# Thermocouple_Schematic.net
KiCad netlist of a schematic drawn in EasyEDA
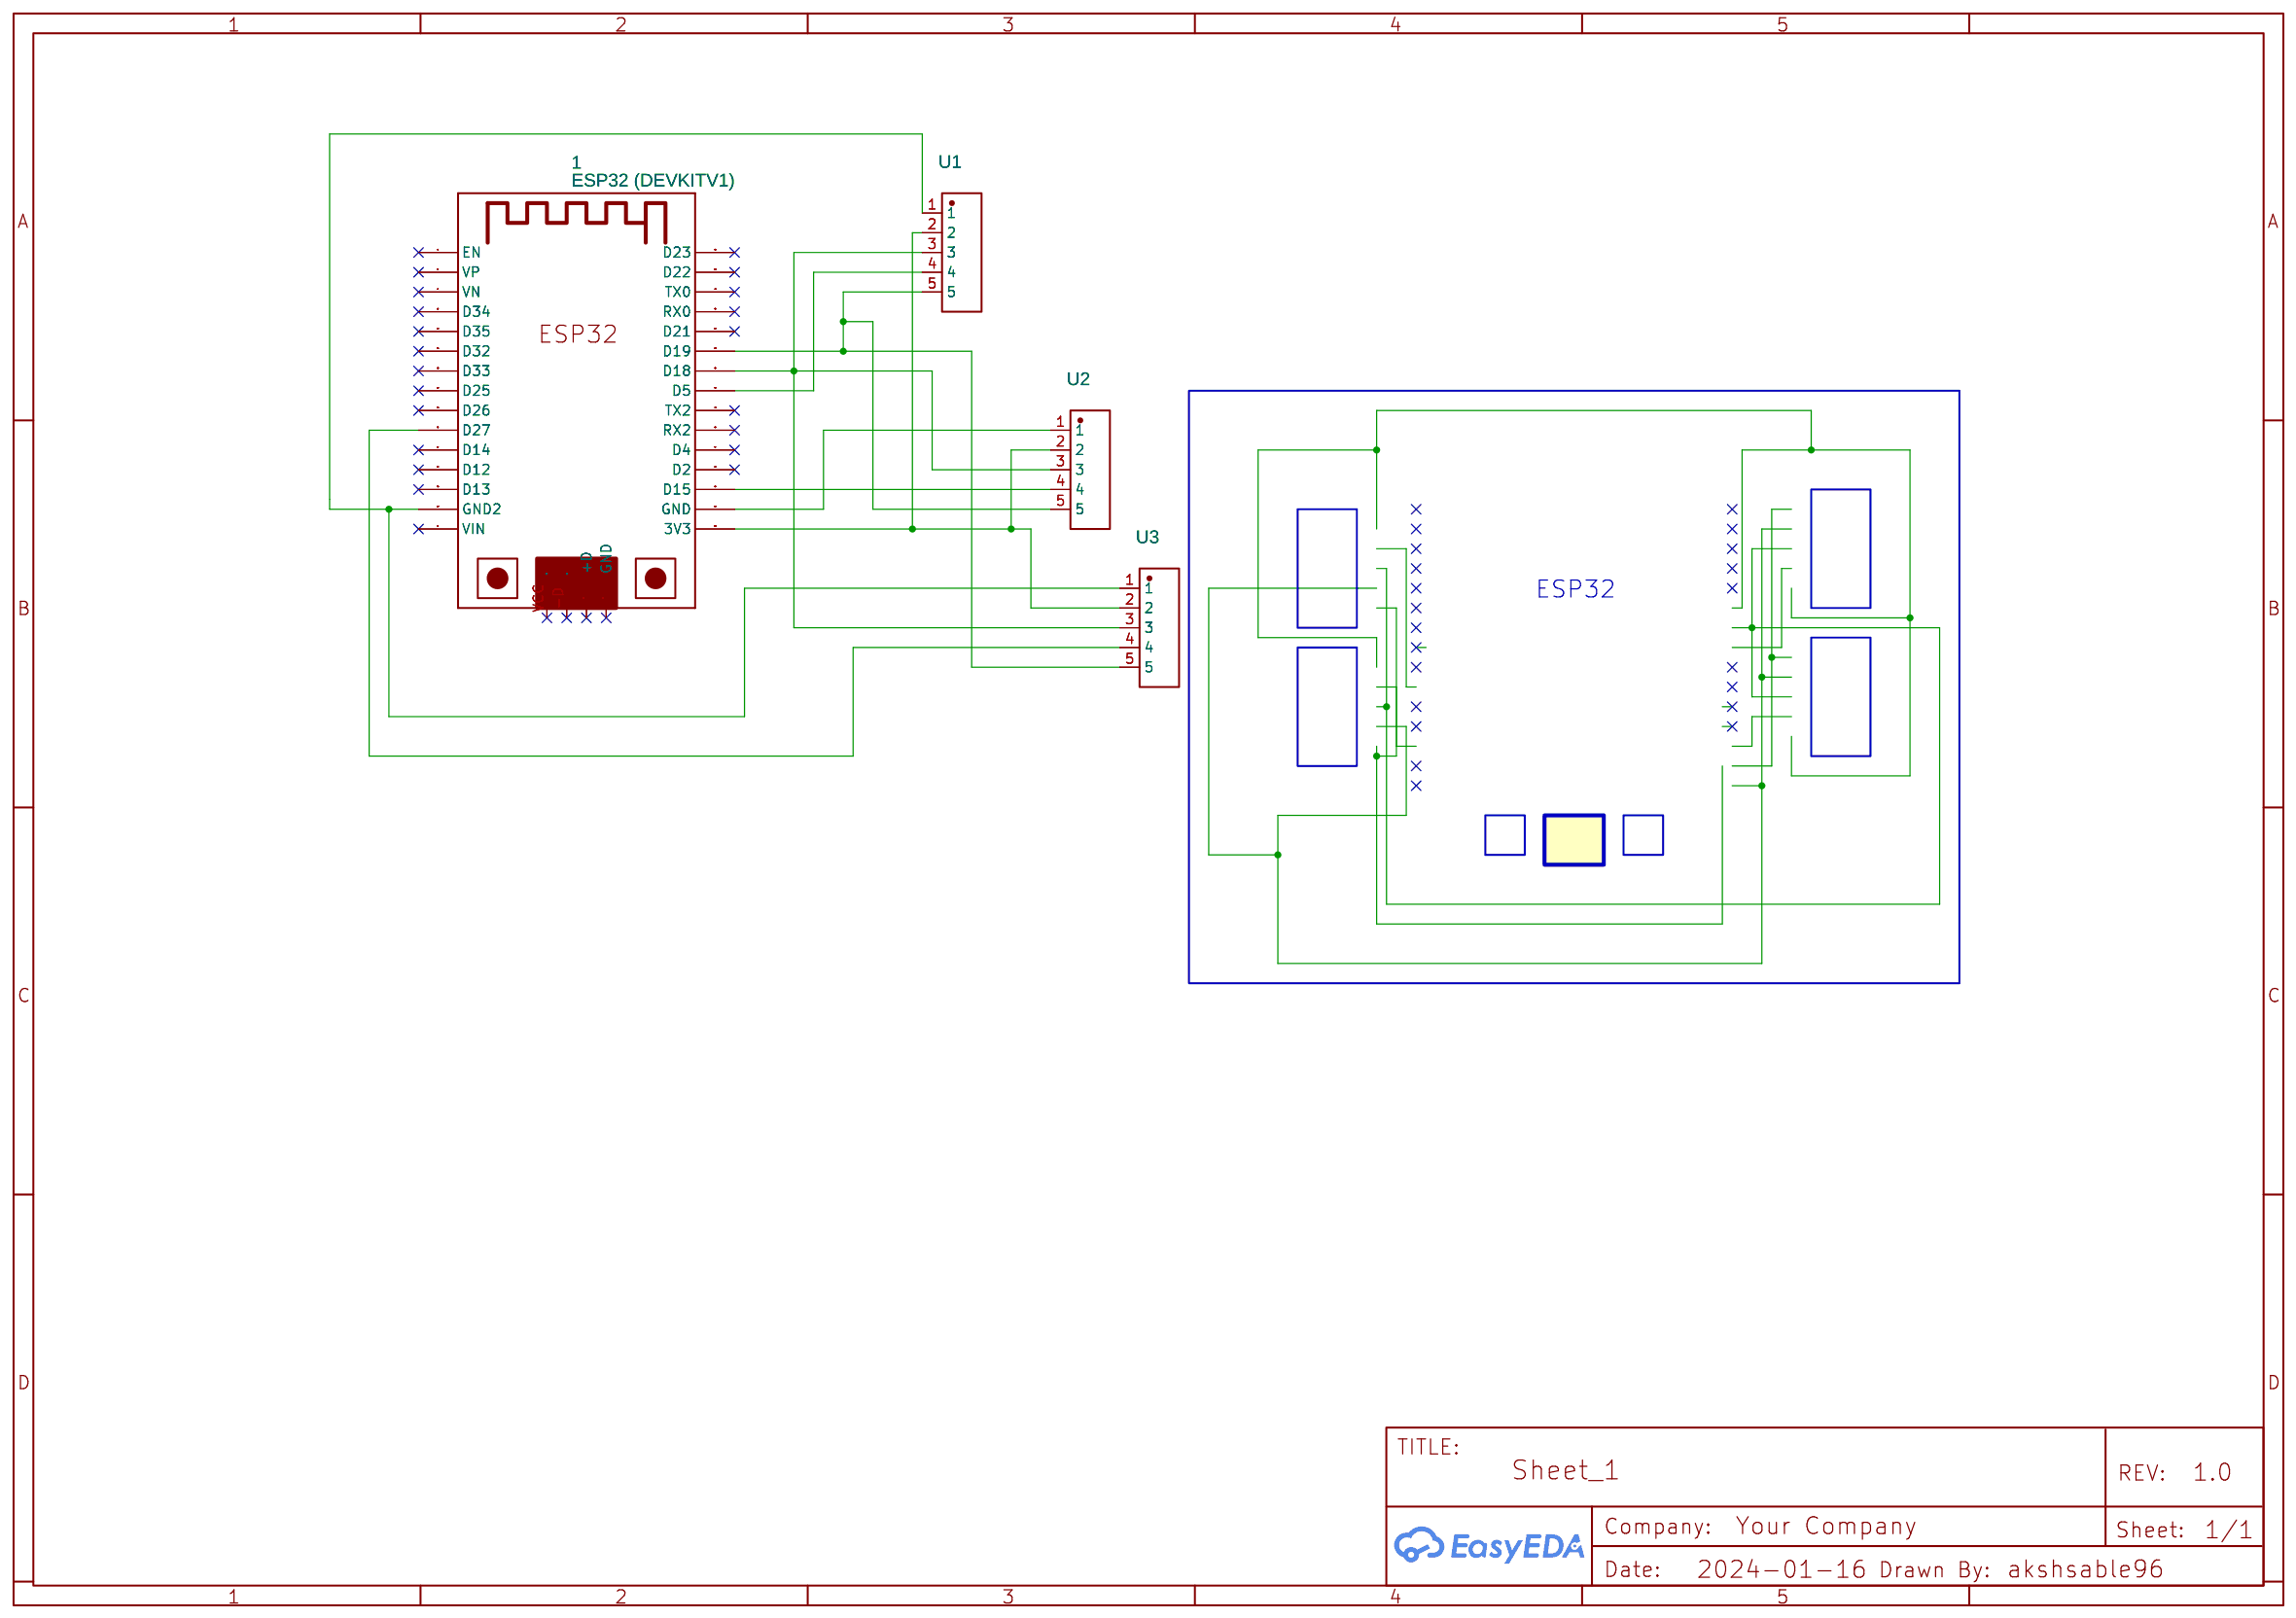
[diagram p0: schematic sheet]

(export (version "E")
  (design (tool "Eeschema 10.0.6"))
  (components
    (comp (ref "1") (value "ESP32 (DEVKITV1)") (libsource (lib "") (part "ESP32-DEVKIT-V1-30PIN")))
    (comp (ref "U1")
      (value "PM2.54-1*5")
      (fields (field (name "Manufacturer") "ZHOURI(洲日)"))
      (libsource (lib "") (part "PM2.54-1*5"))
    )
    (comp (ref "U2")
      (value "PM2.54-1*5")
      (fields (field (name "Manufacturer") "ZHOURI(洲日)"))
      (libsource (lib "") (part "PM2.54-1*5"))
    )
    (comp (ref "U3")
      (value "PM2.54-1*5")
      (fields (field (name "Manufacturer") "ZHOURI(洲日)"))
      (libsource (lib "") (part "PM2.54-1*5"))
    )
  )
  (nets
    (net (code "1") (name "Net-(1-Pad3V3)") (class "Default")
      (node (ref "1") (pin "3V3") (pinfunction "3V3_3V3") (pintype "unspecified"))
      (node (ref "U1") (pin "2") (pinfunction "2_2") (pintype "unspecified"))
      (node (ref "U2") (pin "2") (pinfunction "2_2") (pintype "unspecified"))
      (node (ref "U3") (pin "2") (pinfunction "2_2") (pintype "unspecified"))
    )
    (net (code "2") (name "Net-(1-PadD5)") (class "Default")
      (node (ref "1") (pin "D5") (pinfunction "D5_D5") (pintype "unspecified"))
      (node (ref "U1") (pin "4") (pinfunction "4_4") (pintype "unspecified"))
    )
    (net (code "3") (name "Net-(1-PadD15)") (class "Default")
      (node (ref "1") (pin "D15") (pinfunction "D15_D15") (pintype "unspecified"))
      (node (ref "U2") (pin "4") (pinfunction "4_4") (pintype "unspecified"))
    )
    (net (code "4") (name "Net-(1-PadD18)") (class "Default")
      (node (ref "1") (pin "D18") (pinfunction "D18_D18") (pintype "unspecified"))
      (node (ref "U1") (pin "3") (pinfunction "3_3") (pintype "unspecified"))
      (node (ref "U2") (pin "3") (pinfunction "3_3") (pintype "unspecified"))
      (node (ref "U3") (pin "3") (pinfunction "3_3") (pintype "unspecified"))
    )
    (net (code "5") (name "Net-(1-PadD19)") (class "Default")
      (node (ref "1") (pin "D19") (pinfunction "D19_D19") (pintype "unspecified"))
      (node (ref "U1") (pin "5") (pinfunction "5_5") (pintype "unspecified"))
      (node (ref "U2") (pin "5") (pinfunction "5_5") (pintype "unspecified"))
      (node (ref "U3") (pin "5") (pinfunction "5_5") (pintype "unspecified"))
    )
    (net (code "6") (name "Net-(1-PadD27)") (class "Default")
      (node (ref "1") (pin "D27") (pinfunction "D27_D27") (pintype "unspecified"))
      (node (ref "U3") (pin "4") (pinfunction "4_4") (pintype "unspecified"))
    )
    (net (code "7") (name "Net-(1-PadGND)") (class "Default")
      (node (ref "1") (pin "GND") (pinfunction "GND_GND") (pintype "unspecified"))
      (node (ref "U2") (pin "1") (pinfunction "1_1") (pintype "unspecified"))
    )
    (net (code "8") (name "Net-(1-PadGND2)") (class "Default")
      (node (ref "1") (pin "GND2") (pinfunction "GND2_GND2") (pintype "unspecified"))
      (node (ref "U1") (pin "1") (pinfunction "1_1") (pintype "unspecified"))
      (node (ref "U3") (pin "1") (pinfunction "1_1") (pintype "unspecified"))
    )
    (net (code "9") (name "unconnected-(1-+D-Pad38)") (class "Default")
      (node (ref "1") (pin "38") (pinfunction "+D_38") (pintype "unspecified+no_connect"))
    )
    (net (code "10") (name "unconnected-(1-36-PadVCC)") (class "Default")
      (node (ref "1") (pin "VCC") (pinfunction "36_VCC") (pintype "unspecified+no_connect"))
    )
    (net (code "11") (name "unconnected-(1-37-Pad-D)") (class "Default")
      (node (ref "1") (pin "-D") (pinfunction "37_-D") (pintype "unspecified+no_connect"))
    )
    (net (code "12") (name "unconnected-(1-GND-Pad39)") (class "Default")
      (node (ref "1") (pin "39") (pinfunction "GND_39") (pintype "unspecified+no_connect"))
    )
    (net (code "13") (name "unconnected-(1-PadD2)") (class "Default")
      (node (ref "1") (pin "D2") (pinfunction "D2_D2") (pintype "unspecified+no_connect"))
    )
    (net (code "14") (name "unconnected-(1-PadD4)") (class "Default")
      (node (ref "1") (pin "D4") (pinfunction "D4_D4") (pintype "unspecified+no_connect"))
    )
    (net (code "15") (name "unconnected-(1-PadD12)") (class "Default")
      (node (ref "1") (pin "D12") (pinfunction "D12_D12") (pintype "unspecified+no_connect"))
    )
    (net (code "16") (name "unconnected-(1-PadD13)") (class "Default")
      (node (ref "1") (pin "D13") (pinfunction "D13_D13") (pintype "unspecified+no_connect"))
    )
    (net (code "17") (name "unconnected-(1-PadD14)") (class "Default")
      (node (ref "1") (pin "D14") (pinfunction "D14_D14") (pintype "unspecified+no_connect"))
    )
    (net (code "18") (name "unconnected-(1-PadD21)") (class "Default")
      (node (ref "1") (pin "D21") (pinfunction "D21_D21") (pintype "unspecified+no_connect"))
    )
    (net (code "19") (name "unconnected-(1-PadD22)") (class "Default")
      (node (ref "1") (pin "D22") (pinfunction "D22_D22") (pintype "unspecified+no_connect"))
    )
    (net (code "20") (name "unconnected-(1-PadD23)") (class "Default")
      (node (ref "1") (pin "D23") (pinfunction "D23_D23") (pintype "unspecified+no_connect"))
    )
    (net (code "21") (name "unconnected-(1-PadD25)") (class "Default")
      (node (ref "1") (pin "D25") (pinfunction "D25_D25") (pintype "unspecified+no_connect"))
    )
    (net (code "22") (name "unconnected-(1-PadD26)") (class "Default")
      (node (ref "1") (pin "D26") (pinfunction "D26_D26") (pintype "unspecified+no_connect"))
    )
    (net (code "23") (name "unconnected-(1-PadD32)") (class "Default")
      (node (ref "1") (pin "D32") (pinfunction "D32_D32") (pintype "unspecified+no_connect"))
    )
    (net (code "24") (name "unconnected-(1-PadD33)") (class "Default")
      (node (ref "1") (pin "D33") (pinfunction "D33_D33") (pintype "unspecified+no_connect"))
    )
    (net (code "25") (name "unconnected-(1-PadD34)") (class "Default")
      (node (ref "1") (pin "D34") (pinfunction "D34_D34") (pintype "unspecified+no_connect"))
    )
    (net (code "26") (name "unconnected-(1-PadD35)") (class "Default")
      (node (ref "1") (pin "D35") (pinfunction "D35_D35") (pintype "unspecified+no_connect"))
    )
    (net (code "27") (name "unconnected-(1-PadEN)") (class "Default")
      (node (ref "1") (pin "EN") (pinfunction "EN_EN") (pintype "unspecified+no_connect"))
    )
    (net (code "28") (name "unconnected-(1-PadRX0)") (class "Default")
      (node (ref "1") (pin "RX0") (pinfunction "RX0_RX0") (pintype "unspecified+no_connect"))
    )
    (net (code "29") (name "unconnected-(1-PadRX2)") (class "Default")
      (node (ref "1") (pin "RX2") (pinfunction "RX2_RX2") (pintype "unspecified+no_connect"))
    )
    (net (code "30") (name "unconnected-(1-PadTX0)") (class "Default")
      (node (ref "1") (pin "TX0") (pinfunction "TX0_TX0") (pintype "unspecified+no_connect"))
    )
    (net (code "31") (name "unconnected-(1-PadTX2)") (class "Default")
      (node (ref "1") (pin "TX2") (pinfunction "TX2_TX2") (pintype "unspecified+no_connect"))
    )
    (net (code "32") (name "unconnected-(1-PadVIN)") (class "Default")
      (node (ref "1") (pin "VIN") (pinfunction "VIN_VIN") (pintype "unspecified+no_connect"))
    )
    (net (code "33") (name "unconnected-(1-PadVN)") (class "Default")
      (node (ref "1") (pin "VN") (pinfunction "VN_VN") (pintype "unspecified+no_connect"))
    )
    (net (code "34") (name "unconnected-(1-PadVP)") (class "Default")
      (node (ref "1") (pin "VP") (pinfunction "VP_VP") (pintype "unspecified+no_connect"))
    )
  )
)
